# MRCS-IOX32.net
KiCad netlist of a schematic drawn in EAGLE
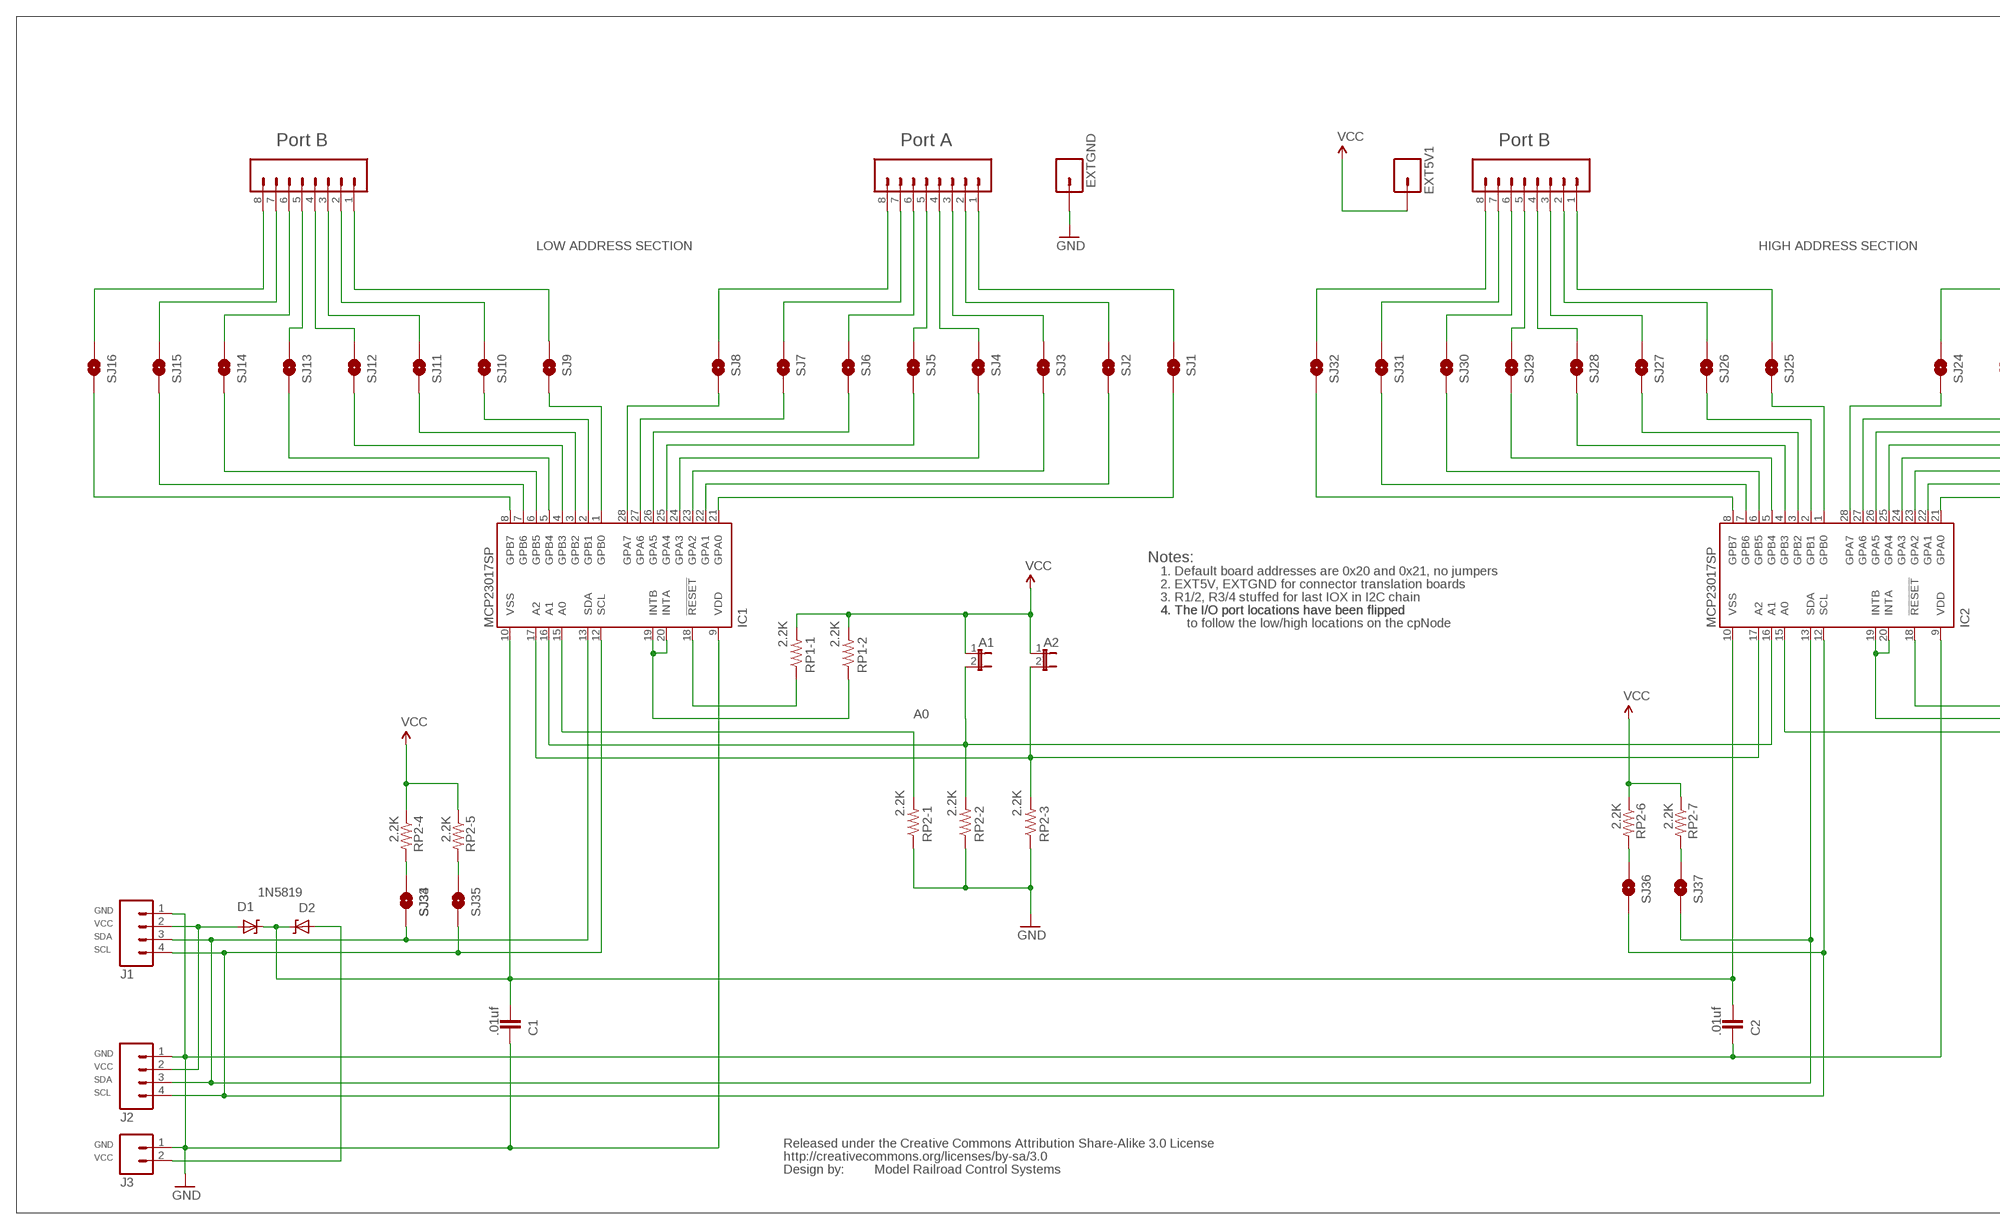
[diagram p0: schematic, sheet 1, part 1 of 2]
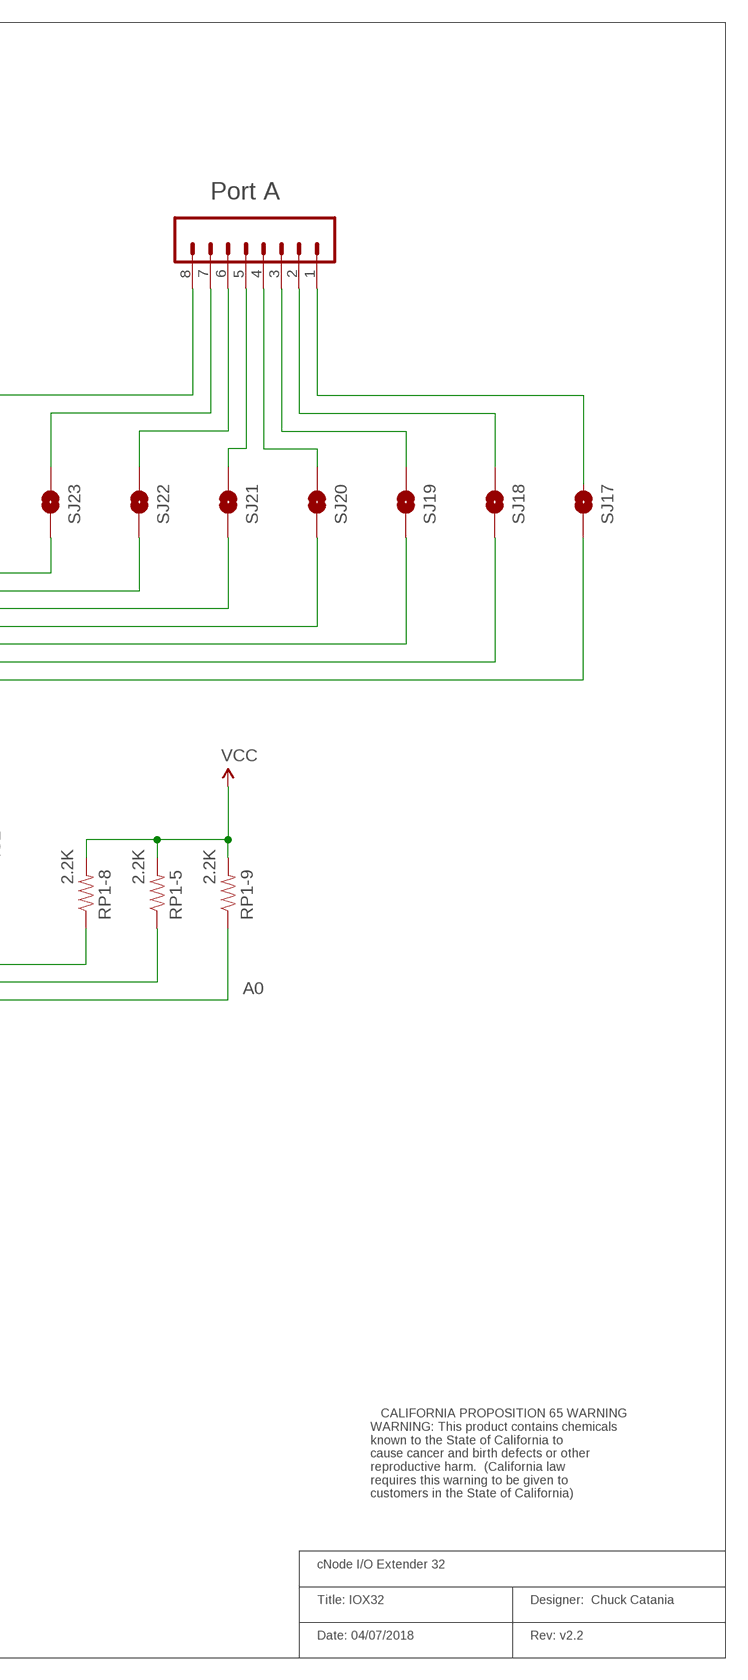
[diagram p1: schematic, sheet 1, part 2 of 2]

(export (version "E")
  (design (tool "Eeschema 10.0.6"))
  (components
    (comp (ref "A1")
      (value "JUMPER-2PTH")
      (footprint "eagle-import:1X02")
      (libsource (lib "eagle-import") (part "JUMPER-2PTH"))
    )
    (comp (ref "A2")
      (value "JUMPER-2PTH")
      (footprint "eagle-import:1X02")
      (libsource (lib "eagle-import") (part "JUMPER-2PTH"))
    )
    (comp (ref "C1")
      (value ".01uf")
      (footprint "eagle-import:AXIAL-5MM")
      (libsource (lib "eagle-import") (part "CAP_"))
    )
    (comp (ref "C2")
      (value ".01uf")
      (footprint "eagle-import:AXIAL-5MM")
      (libsource (lib "eagle-import") (part "CAP_"))
    )
    (comp (ref "D1")
      (value "DIODE-ZENERPTH")
      (footprint "eagle-import:DIODE-ZENER")
      (libsource (lib "eagle-import") (part "DIODE-ZENERPTH"))
    )
    (comp (ref "D2")
      (value "DIODE-ZENERPTH")
      (footprint "eagle-import:DIODE-ZENER")
      (libsource (lib "eagle-import") (part "DIODE-ZENERPTH"))
    )
    (comp (ref "EXT5V1")
      (value "M01PTH_LONGPAD")
      (footprint "eagle-import:1X01_LONGPAD")
      (libsource (lib "eagle-import") (part "M01PTH_LONGPAD"))
    )
    (comp (ref "EXTGND")
      (value "M01PTH_LONGPAD")
      (footprint "eagle-import:1X01_LONGPAD")
      (libsource (lib "eagle-import") (part "M01PTH_LONGPAD"))
    )
    (comp (ref "IC1")
      (value "MCP23017SP")
      (footprint "eagle-import:DIL28-3")
      (fields (field (name "MF") "MICROCHIP") (field (name "MPN") "MCP23017-E/SP"))
      (libsource (lib "eagle-import") (part "MCP23017SP"))
    )
    (comp (ref "IC2")
      (value "MCP23017SP")
      (footprint "eagle-import:DIL28-3")
      (fields (field (name "MF") "MICROCHIP") (field (name "MPN") "MCP23017-E/SP"))
      (libsource (lib "eagle-import") (part "MCP23017SP"))
    )
    (comp (ref "J1")
      (value "M04PTH")
      (footprint "eagle-import:1X04")
      (libsource (lib "eagle-import") (part "M04PTH"))
    )
    (comp (ref "J2")
      (value "M04PTH")
      (footprint "eagle-import:1X04")
      (libsource (lib "eagle-import") (part "M04PTH"))
    )
    (comp (ref "J3")
      (value "M021X02_NO_SILK")
      (footprint "eagle-import:1X02_NO_SILK")
      (libsource (lib "eagle-import") (part "M021X02_NO_SILK"))
    )
    (comp (ref "PORTA")
      (value "M081X08")
      (footprint "eagle-import:1X08")
      (libsource (lib "eagle-import") (part "M081X08"))
    )
    (comp (ref "PORTA1")
      (value "M081X08")
      (footprint "eagle-import:1X08")
      (libsource (lib "eagle-import") (part "M081X08"))
    )
    (comp (ref "PORTB")
      (value "M081X08")
      (footprint "eagle-import:1X08")
      (libsource (lib "eagle-import") (part "M081X08"))
    )
    (comp (ref "PORTB1")
      (value "M081X08")
      (footprint "eagle-import:1X08")
      (libsource (lib "eagle-import") (part "M081X08"))
    )
    (comp (ref "RP1-1")
      (value "2.2K")
      (footprint "eagle-import:AXIAL-0.4")
      (libsource (lib "eagle-import") (part "RESISTORPTH-1/4W"))
    )
    (comp (ref "RP1-2")
      (value "2.2K")
      (footprint "eagle-import:AXIAL-0.4")
      (libsource (lib "eagle-import") (part "RESISTORPTH-1/4W"))
    )
    (comp (ref "RP1-5")
      (value "2.2K")
      (footprint "eagle-import:AXIAL-0.4")
      (libsource (lib "eagle-import") (part "RESISTORPTH-1/4W"))
    )
    (comp (ref "RP1-8")
      (value "2.2K")
      (footprint "eagle-import:AXIAL-0.4")
      (libsource (lib "eagle-import") (part "RESISTORPTH-1/4W"))
    )
    (comp (ref "RP1-9")
      (value "2.2K")
      (footprint "eagle-import:AXIAL-0.4")
      (libsource (lib "eagle-import") (part "RESISTORPTH-1/4W"))
    )
    (comp (ref "RP2-1")
      (value "2.2K")
      (footprint "eagle-import:AXIAL-0.4")
      (libsource (lib "eagle-import") (part "RESISTORPTH-1/4W"))
    )
    (comp (ref "RP2-2")
      (value "2.2K")
      (footprint "eagle-import:AXIAL-0.4")
      (libsource (lib "eagle-import") (part "RESISTORPTH-1/4W"))
    )
    (comp (ref "RP2-3")
      (value "2.2K")
      (footprint "eagle-import:AXIAL-0.4")
      (libsource (lib "eagle-import") (part "RESISTORPTH-1/4W"))
    )
    (comp (ref "RP2-4")
      (value "2.2K")
      (footprint "eagle-import:AXIAL-0.4")
      (libsource (lib "eagle-import") (part "RESISTORPTH-1/4W"))
    )
    (comp (ref "RP2-5")
      (value "2.2K")
      (footprint "eagle-import:AXIAL-0.4")
      (libsource (lib "eagle-import") (part "RESISTORPTH-1/4W"))
    )
    (comp (ref "RP2-6")
      (value "2.2K")
      (footprint "eagle-import:AXIAL-0.4")
      (libsource (lib "eagle-import") (part "RESISTORPTH-1/4W"))
    )
    (comp (ref "RP2-7")
      (value "2.2K")
      (footprint "eagle-import:AXIAL-0.4")
      (libsource (lib "eagle-import") (part "RESISTORPTH-1/4W"))
    )
    (comp (ref "SJ1")
      (value "PAD-SOLDERJUMPERNC")
      (footprint "eagle-import:2P-SMD-2X3.3")
      (libsource (lib "eagle-import") (part "PAD-SOLDERJUMPERNC"))
    )
    (comp (ref "SJ2")
      (value "PAD-SOLDERJUMPERNC")
      (footprint "eagle-import:2P-SMD-2X3.3")
      (libsource (lib "eagle-import") (part "PAD-SOLDERJUMPERNC"))
    )
    (comp (ref "SJ3")
      (value "PAD-SOLDERJUMPERNC")
      (footprint "eagle-import:2P-SMD-2X3.3")
      (libsource (lib "eagle-import") (part "PAD-SOLDERJUMPERNC"))
    )
    (comp (ref "SJ4")
      (value "PAD-SOLDERJUMPERNC")
      (footprint "eagle-import:2P-SMD-2X3.3")
      (libsource (lib "eagle-import") (part "PAD-SOLDERJUMPERNC"))
    )
    (comp (ref "SJ5")
      (value "PAD-SOLDERJUMPERNC")
      (footprint "eagle-import:2P-SMD-2X3.3")
      (libsource (lib "eagle-import") (part "PAD-SOLDERJUMPERNC"))
    )
    (comp (ref "SJ6")
      (value "PAD-SOLDERJUMPERNC")
      (footprint "eagle-import:2P-SMD-2X3.3")
      (libsource (lib "eagle-import") (part "PAD-SOLDERJUMPERNC"))
    )
    (comp (ref "SJ7")
      (value "PAD-SOLDERJUMPERNC")
      (footprint "eagle-import:2P-SMD-2X3.3")
      (libsource (lib "eagle-import") (part "PAD-SOLDERJUMPERNC"))
    )
    (comp (ref "SJ8")
      (value "PAD-SOLDERJUMPERNC")
      (footprint "eagle-import:2P-SMD-2X3.3")
      (libsource (lib "eagle-import") (part "PAD-SOLDERJUMPERNC"))
    )
    (comp (ref "SJ9")
      (value "PAD-SOLDERJUMPERNC")
      (footprint "eagle-import:2P-SMD-2X3.3")
      (libsource (lib "eagle-import") (part "PAD-SOLDERJUMPERNC"))
    )
    (comp (ref "SJ10")
      (value "PAD-SOLDERJUMPERNC")
      (footprint "eagle-import:2P-SMD-2X3.3")
      (libsource (lib "eagle-import") (part "PAD-SOLDERJUMPERNC"))
    )
    (comp (ref "SJ11")
      (value "PAD-SOLDERJUMPERNC")
      (footprint "eagle-import:2P-SMD-2X3.3")
      (libsource (lib "eagle-import") (part "PAD-SOLDERJUMPERNC"))
    )
    (comp (ref "SJ12")
      (value "PAD-SOLDERJUMPERNC")
      (footprint "eagle-import:2P-SMD-2X3.3")
      (libsource (lib "eagle-import") (part "PAD-SOLDERJUMPERNC"))
    )
    (comp (ref "SJ13")
      (value "PAD-SOLDERJUMPERNC")
      (footprint "eagle-import:2P-SMD-2X3.3")
      (libsource (lib "eagle-import") (part "PAD-SOLDERJUMPERNC"))
    )
    (comp (ref "SJ14")
      (value "PAD-SOLDERJUMPERNC")
      (footprint "eagle-import:2P-SMD-2X3.3")
      (libsource (lib "eagle-import") (part "PAD-SOLDERJUMPERNC"))
    )
    (comp (ref "SJ15")
      (value "PAD-SOLDERJUMPERNC")
      (footprint "eagle-import:2P-SMD-2X3.3")
      (libsource (lib "eagle-import") (part "PAD-SOLDERJUMPERNC"))
    )
    (comp (ref "SJ16")
      (value "PAD-SOLDERJUMPERNC")
      (footprint "eagle-import:2P-SMD-2X3.3")
      (libsource (lib "eagle-import") (part "PAD-SOLDERJUMPERNC"))
    )
    (comp (ref "SJ17")
      (value "PAD-SOLDERJUMPERNC")
      (footprint "eagle-import:2P-SMD-2X3.3")
      (libsource (lib "eagle-import") (part "PAD-SOLDERJUMPERNC"))
    )
    (comp (ref "SJ18")
      (value "PAD-SOLDERJUMPERNC")
      (footprint "eagle-import:2P-SMD-2X3.3")
      (libsource (lib "eagle-import") (part "PAD-SOLDERJUMPERNC"))
    )
    (comp (ref "SJ19")
      (value "PAD-SOLDERJUMPERNC")
      (footprint "eagle-import:2P-SMD-2X3.3")
      (libsource (lib "eagle-import") (part "PAD-SOLDERJUMPERNC"))
    )
    (comp (ref "SJ20")
      (value "PAD-SOLDERJUMPERNC")
      (footprint "eagle-import:2P-SMD-2X3.3")
      (libsource (lib "eagle-import") (part "PAD-SOLDERJUMPERNC"))
    )
    (comp (ref "SJ21")
      (value "PAD-SOLDERJUMPERNC")
      (footprint "eagle-import:2P-SMD-2X3.3")
      (libsource (lib "eagle-import") (part "PAD-SOLDERJUMPERNC"))
    )
    (comp (ref "SJ22")
      (value "PAD-SOLDERJUMPERNC")
      (footprint "eagle-import:2P-SMD-2X3.3")
      (libsource (lib "eagle-import") (part "PAD-SOLDERJUMPERNC"))
    )
    (comp (ref "SJ23")
      (value "PAD-SOLDERJUMPERNC")
      (footprint "eagle-import:2P-SMD-2X3.3")
      (libsource (lib "eagle-import") (part "PAD-SOLDERJUMPERNC"))
    )
    (comp (ref "SJ24")
      (value "PAD-SOLDERJUMPERNC")
      (footprint "eagle-import:2P-SMD-2X3.3")
      (libsource (lib "eagle-import") (part "PAD-SOLDERJUMPERNC"))
    )
    (comp (ref "SJ25")
      (value "PAD-SOLDERJUMPERNC")
      (footprint "eagle-import:2P-SMD-2X3.3")
      (libsource (lib "eagle-import") (part "PAD-SOLDERJUMPERNC"))
    )
    (comp (ref "SJ26")
      (value "PAD-SOLDERJUMPERNC")
      (footprint "eagle-import:2P-SMD-2X3.3")
      (libsource (lib "eagle-import") (part "PAD-SOLDERJUMPERNC"))
    )
    (comp (ref "SJ27")
      (value "PAD-SOLDERJUMPERNC")
      (footprint "eagle-import:2P-SMD-2X3.3")
      (libsource (lib "eagle-import") (part "PAD-SOLDERJUMPERNC"))
    )
    (comp (ref "SJ28")
      (value "PAD-SOLDERJUMPERNC")
      (footprint "eagle-import:2P-SMD-2X3.3")
      (libsource (lib "eagle-import") (part "PAD-SOLDERJUMPERNC"))
    )
    (comp (ref "SJ29")
      (value "PAD-SOLDERJUMPERNC")
      (footprint "eagle-import:2P-SMD-2X3.3")
      (libsource (lib "eagle-import") (part "PAD-SOLDERJUMPERNC"))
    )
    (comp (ref "SJ30")
      (value "PAD-SOLDERJUMPERNC")
      (footprint "eagle-import:2P-SMD-2X3.3")
      (libsource (lib "eagle-import") (part "PAD-SOLDERJUMPERNC"))
    )
    (comp (ref "SJ31")
      (value "PAD-SOLDERJUMPERNC")
      (footprint "eagle-import:2P-SMD-2X3.3")
      (libsource (lib "eagle-import") (part "PAD-SOLDERJUMPERNC"))
    )
    (comp (ref "SJ32")
      (value "PAD-SOLDERJUMPERNC")
      (footprint "eagle-import:2P-SMD-2X3.3")
      (libsource (lib "eagle-import") (part "PAD-SOLDERJUMPERNC"))
    )
    (comp (ref "SJ33")
      (value "PAD-SOLDERJUMPERNC")
      (footprint "eagle-import:2P-SMD-2X3.3")
      (libsource (lib "eagle-import") (part "PAD-SOLDERJUMPERNC"))
    )
    (comp (ref "SJ34")
      (value "PAD-SOLDERJUMPERNC")
      (footprint "eagle-import:2P-SMD-2X3.3")
      (libsource (lib "eagle-import") (part "PAD-SOLDERJUMPERNC"))
    )
    (comp (ref "SJ35")
      (value "PAD-SOLDERJUMPERNC")
      (footprint "eagle-import:2P-SMD-2X3.3")
      (libsource (lib "eagle-import") (part "PAD-SOLDERJUMPERNC"))
    )
    (comp (ref "SJ36")
      (value "PAD-SOLDERJUMPERNC")
      (footprint "eagle-import:2P-SMD-2X3.3")
      (libsource (lib "eagle-import") (part "PAD-SOLDERJUMPERNC"))
    )
    (comp (ref "SJ37")
      (value "PAD-SOLDERJUMPERNC")
      (footprint "eagle-import:2P-SMD-2X3.3")
      (libsource (lib "eagle-import") (part "PAD-SOLDERJUMPERNC"))
    )
    (comp (ref "U$1")
      (value "CREATIVE_COMMONS")
      (footprint "eagle-import:CREATIVE_COMMONS")
      (libsource (lib "eagle-import") (part "CREATIVE_COMMONS"))
    )
    (comp (ref "U$2")
      (value "CA-PROP65WARNING")
      (footprint "eagle-import:CA-PROP65WARNING")
      (libsource (lib "eagle-import") (part "CA-PROP65WARNING"))
    )
  )
  (nets
    (net (code "1") (name "GND") (class "Default")
      (node (ref "C1") (pin "P$1") (pinfunction "1_P$1") (pintype "passive"))
      (node (ref "C2") (pin "P$1") (pinfunction "1_P$1") (pintype "passive"))
      (node (ref "EXTGND") (pin "1") (pinfunction "1_1") (pintype "passive"))
      (node (ref "IC1") (pin "9") (pinfunction "VDD_9") (pintype "power_in"))
      (node (ref "IC2") (pin "9") (pinfunction "VDD_9") (pintype "power_in"))
      (node (ref "J1") (pin "1") (pinfunction "1_1") (pintype "passive"))
      (node (ref "J2") (pin "1") (pinfunction "1_1") (pintype "passive"))
      (node (ref "J3") (pin "1") (pinfunction "1_1") (pintype "passive"))
      (node (ref "RP2-1") (pin "P$1") (pinfunction "1_P$1") (pintype "passive"))
      (node (ref "RP2-2") (pin "P$1") (pinfunction "1_P$1") (pintype "passive"))
      (node (ref "RP2-3") (pin "P$1") (pinfunction "1_P$1") (pintype "passive"))
    )
    (net (code "2") (name "Net-(C1-2)") (class "Default")
      (node (ref "C1") (pin "P$2") (pinfunction "2_P$2") (pintype "passive"))
      (node (ref "C2") (pin "P$2") (pinfunction "2_P$2") (pintype "passive"))
      (node (ref "D1") (pin "P$1") (pinfunction "C_P$1") (pintype "passive"))
      (node (ref "D2") (pin "P$1") (pinfunction "C_P$1") (pintype "passive"))
      (node (ref "IC1") (pin "10") (pinfunction "VSS_10") (pintype "power_in"))
      (node (ref "IC2") (pin "10") (pinfunction "VSS_10") (pintype "power_in"))
    )
    (net (code "3") (name "Net-(D1-A)") (class "Default")
      (node (ref "D1") (pin "P$2") (pinfunction "A_P$2") (pintype "passive"))
      (node (ref "J1") (pin "2") (pinfunction "2_2") (pintype "passive"))
      (node (ref "J2") (pin "2") (pinfunction "2_2") (pintype "passive"))
    )
    (net (code "4") (name "Net-(D2-A)") (class "Default")
      (node (ref "D2") (pin "P$2") (pinfunction "A_P$2") (pintype "passive"))
      (node (ref "J3") (pin "2") (pinfunction "2_2") (pintype "passive"))
    )
    (net (code "5") (name "Net-(IC1-A0)") (class "Default")
      (node (ref "IC1") (pin "15") (pinfunction "A0_15") (pintype "input"))
      (node (ref "RP2-1") (pin "P$2") (pinfunction "2_P$2") (pintype "passive"))
    )
    (net (code "6") (name "Net-(IC1-A1)") (class "Default")
      (node (ref "A1") (pin "2") (pinfunction "2_2") (pintype "passive"))
      (node (ref "IC1") (pin "16") (pinfunction "A1_16") (pintype "input"))
      (node (ref "IC2") (pin "16") (pinfunction "A1_16") (pintype "input"))
      (node (ref "RP2-2") (pin "P$2") (pinfunction "2_P$2") (pintype "passive"))
    )
    (net (code "7") (name "Net-(IC1-A2)") (class "Default")
      (node (ref "A2") (pin "2") (pinfunction "2_2") (pintype "passive"))
      (node (ref "IC1") (pin "17") (pinfunction "A2_17") (pintype "input"))
      (node (ref "IC2") (pin "17") (pinfunction "A2_17") (pintype "input"))
      (node (ref "RP2-3") (pin "P$2") (pinfunction "2_P$2") (pintype "passive"))
    )
    (net (code "8") (name "Net-(IC1-GPA0)") (class "Default")
      (node (ref "IC1") (pin "21") (pinfunction "GPA0_21") (pintype "bidirectional"))
      (node (ref "SJ1") (pin "2") (pinfunction "2_2") (pintype "passive"))
    )
    (net (code "9") (name "Net-(IC1-GPA1)") (class "Default")
      (node (ref "IC1") (pin "22") (pinfunction "GPA1_22") (pintype "bidirectional"))
      (node (ref "SJ2") (pin "2") (pinfunction "2_2") (pintype "passive"))
    )
    (net (code "10") (name "Net-(IC1-GPA2)") (class "Default")
      (node (ref "IC1") (pin "23") (pinfunction "GPA2_23") (pintype "bidirectional"))
      (node (ref "SJ3") (pin "2") (pinfunction "2_2") (pintype "passive"))
    )
    (net (code "11") (name "Net-(IC1-GPA3)") (class "Default")
      (node (ref "IC1") (pin "24") (pinfunction "GPA3_24") (pintype "bidirectional"))
      (node (ref "SJ4") (pin "2") (pinfunction "2_2") (pintype "passive"))
    )
    (net (code "12") (name "Net-(IC1-GPA4)") (class "Default")
      (node (ref "IC1") (pin "25") (pinfunction "GPA4_25") (pintype "bidirectional"))
      (node (ref "SJ5") (pin "2") (pinfunction "2_2") (pintype "passive"))
    )
    (net (code "13") (name "Net-(IC1-GPA5)") (class "Default")
      (node (ref "IC1") (pin "26") (pinfunction "GPA5_26") (pintype "bidirectional"))
      (node (ref "SJ6") (pin "2") (pinfunction "2_2") (pintype "passive"))
    )
    (net (code "14") (name "Net-(IC1-GPA6)") (class "Default")
      (node (ref "IC1") (pin "27") (pinfunction "GPA6_27") (pintype "bidirectional"))
      (node (ref "SJ7") (pin "2") (pinfunction "2_2") (pintype "passive"))
    )
    (net (code "15") (name "Net-(IC1-GPA7)") (class "Default")
      (node (ref "IC1") (pin "28") (pinfunction "GPA7_28") (pintype "bidirectional"))
      (node (ref "SJ8") (pin "2") (pinfunction "2_2") (pintype "passive"))
    )
    (net (code "16") (name "Net-(IC1-GPB0)") (class "Default")
      (node (ref "IC1") (pin "1") (pinfunction "GPB0_1") (pintype "bidirectional"))
      (node (ref "SJ9") (pin "2") (pinfunction "2_2") (pintype "passive"))
    )
    (net (code "17") (name "Net-(IC1-GPB1)") (class "Default")
      (node (ref "IC1") (pin "2") (pinfunction "GPB1_2") (pintype "bidirectional"))
      (node (ref "SJ10") (pin "2") (pinfunction "2_2") (pintype "passive"))
    )
    (net (code "18") (name "Net-(IC1-GPB2)") (class "Default")
      (node (ref "IC1") (pin "3") (pinfunction "GPB2_3") (pintype "bidirectional"))
      (node (ref "SJ11") (pin "2") (pinfunction "2_2") (pintype "passive"))
    )
    (net (code "19") (name "Net-(IC1-GPB3)") (class "Default")
      (node (ref "IC1") (pin "4") (pinfunction "GPB3_4") (pintype "bidirectional"))
      (node (ref "SJ12") (pin "2") (pinfunction "2_2") (pintype "passive"))
    )
    (net (code "20") (name "Net-(IC1-GPB4)") (class "Default")
      (node (ref "IC1") (pin "5") (pinfunction "GPB4_5") (pintype "bidirectional"))
      (node (ref "SJ13") (pin "2") (pinfunction "2_2") (pintype "passive"))
    )
    (net (code "21") (name "Net-(IC1-GPB5)") (class "Default")
      (node (ref "IC1") (pin "6") (pinfunction "GPB5_6") (pintype "bidirectional"))
      (node (ref "SJ14") (pin "2") (pinfunction "2_2") (pintype "passive"))
    )
    (net (code "22") (name "Net-(IC1-GPB6)") (class "Default")
      (node (ref "IC1") (pin "7") (pinfunction "GPB6_7") (pintype "bidirectional"))
      (node (ref "SJ15") (pin "2") (pinfunction "2_2") (pintype "passive"))
    )
    (net (code "23") (name "Net-(IC1-GPB7)") (class "Default")
      (node (ref "IC1") (pin "8") (pinfunction "GPB7_8") (pintype "bidirectional"))
      (node (ref "SJ16") (pin "2") (pinfunction "2_2") (pintype "passive"))
    )
    (net (code "24") (name "Net-(IC1-INTA)") (class "Default")
      (node (ref "IC1") (pin "19") (pinfunction "INTB_19") (pintype "output"))
      (node (ref "IC1") (pin "20") (pinfunction "INTA_20") (pintype "output"))
      (node (ref "RP1-2") (pin "P$1") (pinfunction "1_P$1") (pintype "passive"))
    )
    (net (code "25") (name "Net-(IC1-SCL)") (class "Default")
      (node (ref "IC1") (pin "12") (pinfunction "SCL_12") (pintype "input"))
      (node (ref "IC2") (pin "12") (pinfunction "SCL_12") (pintype "input"))
      (node (ref "J1") (pin "4") (pinfunction "4_4") (pintype "passive"))
      (node (ref "J2") (pin "4") (pinfunction "4_4") (pintype "passive"))
      (node (ref "SJ35") (pin "2") (pinfunction "2_2") (pintype "passive"))
      (node (ref "SJ36") (pin "2") (pinfunction "2_2") (pintype "passive"))
    )
    (net (code "26") (name "Net-(IC1-SDA)") (class "Default")
      (node (ref "IC1") (pin "13") (pinfunction "SDA_13") (pintype "bidirectional"))
      (node (ref "IC2") (pin "13") (pinfunction "SDA_13") (pintype "bidirectional"))
      (node (ref "J1") (pin "3") (pinfunction "3_3") (pintype "passive"))
      (node (ref "J2") (pin "3") (pinfunction "3_3") (pintype "passive"))
      (node (ref "SJ33") (pin "2") (pinfunction "2_2") (pintype "passive"))
      (node (ref "SJ34") (pin "2") (pinfunction "2_2") (pintype "passive"))
      (node (ref "SJ37") (pin "2") (pinfunction "2_2") (pintype "passive"))
    )
    (net (code "27") (name "Net-(IC1-~{RESET})") (class "Default")
      (node (ref "IC1") (pin "18") (pinfunction "~{RESET}_18") (pintype "input"))
      (node (ref "RP1-1") (pin "P$1") (pinfunction "1_P$1") (pintype "passive"))
    )
    (net (code "28") (name "Net-(IC2-A0)") (class "Default")
      (node (ref "IC2") (pin "15") (pinfunction "A0_15") (pintype "input"))
      (node (ref "RP1-9") (pin "P$1") (pinfunction "1_P$1") (pintype "passive"))
    )
    (net (code "29") (name "Net-(IC2-GPA0)") (class "Default")
      (node (ref "IC2") (pin "21") (pinfunction "GPA0_21") (pintype "bidirectional"))
      (node (ref "SJ17") (pin "2") (pinfunction "2_2") (pintype "passive"))
    )
    (net (code "30") (name "Net-(IC2-GPA1)") (class "Default")
      (node (ref "IC2") (pin "22") (pinfunction "GPA1_22") (pintype "bidirectional"))
      (node (ref "SJ18") (pin "2") (pinfunction "2_2") (pintype "passive"))
    )
    (net (code "31") (name "Net-(IC2-GPA2)") (class "Default")
      (node (ref "IC2") (pin "23") (pinfunction "GPA2_23") (pintype "bidirectional"))
      (node (ref "SJ19") (pin "2") (pinfunction "2_2") (pintype "passive"))
    )
    (net (code "32") (name "Net-(IC2-GPA3)") (class "Default")
      (node (ref "IC2") (pin "24") (pinfunction "GPA3_24") (pintype "bidirectional"))
      (node (ref "SJ20") (pin "2") (pinfunction "2_2") (pintype "passive"))
    )
    (net (code "33") (name "Net-(IC2-GPA4)") (class "Default")
      (node (ref "IC2") (pin "25") (pinfunction "GPA4_25") (pintype "bidirectional"))
      (node (ref "SJ21") (pin "2") (pinfunction "2_2") (pintype "passive"))
    )
    (net (code "34") (name "Net-(IC2-GPA5)") (class "Default")
      (node (ref "IC2") (pin "26") (pinfunction "GPA5_26") (pintype "bidirectional"))
      (node (ref "SJ22") (pin "2") (pinfunction "2_2") (pintype "passive"))
    )
    (net (code "35") (name "Net-(IC2-GPA6)") (class "Default")
      (node (ref "IC2") (pin "27") (pinfunction "GPA6_27") (pintype "bidirectional"))
      (node (ref "SJ23") (pin "2") (pinfunction "2_2") (pintype "passive"))
    )
    (net (code "36") (name "Net-(IC2-GPA7)") (class "Default")
      (node (ref "IC2") (pin "28") (pinfunction "GPA7_28") (pintype "bidirectional"))
      (node (ref "SJ24") (pin "2") (pinfunction "2_2") (pintype "passive"))
    )
    (net (code "37") (name "Net-(IC2-GPB0)") (class "Default")
      (node (ref "IC2") (pin "1") (pinfunction "GPB0_1") (pintype "bidirectional"))
      (node (ref "SJ25") (pin "2") (pinfunction "2_2") (pintype "passive"))
    )
    (net (code "38") (name "Net-(IC2-GPB1)") (class "Default")
      (node (ref "IC2") (pin "2") (pinfunction "GPB1_2") (pintype "bidirectional"))
      (node (ref "SJ26") (pin "2") (pinfunction "2_2") (pintype "passive"))
    )
    (net (code "39") (name "Net-(IC2-GPB2)") (class "Default")
      (node (ref "IC2") (pin "3") (pinfunction "GPB2_3") (pintype "bidirectional"))
      (node (ref "SJ27") (pin "2") (pinfunction "2_2") (pintype "passive"))
    )
    (net (code "40") (name "Net-(IC2-GPB3)") (class "Default")
      (node (ref "IC2") (pin "4") (pinfunction "GPB3_4") (pintype "bidirectional"))
      (node (ref "SJ28") (pin "2") (pinfunction "2_2") (pintype "passive"))
    )
    (net (code "41") (name "Net-(IC2-GPB4)") (class "Default")
      (node (ref "IC2") (pin "5") (pinfunction "GPB4_5") (pintype "bidirectional"))
      (node (ref "SJ29") (pin "2") (pinfunction "2_2") (pintype "passive"))
    )
    (net (code "42") (name "Net-(IC2-GPB5)") (class "Default")
      (node (ref "IC2") (pin "6") (pinfunction "GPB5_6") (pintype "bidirectional"))
      (node (ref "SJ30") (pin "2") (pinfunction "2_2") (pintype "passive"))
    )
    (net (code "43") (name "Net-(IC2-GPB6)") (class "Default")
      (node (ref "IC2") (pin "7") (pinfunction "GPB6_7") (pintype "bidirectional"))
      (node (ref "SJ31") (pin "2") (pinfunction "2_2") (pintype "passive"))
    )
    (net (code "44") (name "Net-(IC2-GPB7)") (class "Default")
      (node (ref "IC2") (pin "8") (pinfunction "GPB7_8") (pintype "bidirectional"))
      (node (ref "SJ32") (pin "2") (pinfunction "2_2") (pintype "passive"))
    )
    (net (code "45") (name "Net-(IC2-INTA)") (class "Default")
      (node (ref "IC2") (pin "19") (pinfunction "INTB_19") (pintype "output"))
      (node (ref "IC2") (pin "20") (pinfunction "INTA_20") (pintype "output"))
      (node (ref "RP1-5") (pin "P$1") (pinfunction "1_P$1") (pintype "passive"))
    )
    (net (code "46") (name "Net-(IC2-~{RESET})") (class "Default")
      (node (ref "IC2") (pin "18") (pinfunction "~{RESET}_18") (pintype "input"))
      (node (ref "RP1-8") (pin "P$1") (pinfunction "1_P$1") (pintype "passive"))
    )
    (net (code "47") (name "Net-(PORTA-Pad1)") (class "Default")
      (node (ref "PORTA") (pin "1") (pinfunction "1_1") (pintype "passive"))
      (node (ref "SJ1") (pin "1") (pinfunction "1_1") (pintype "passive"))
    )
    (net (code "48") (name "Net-(PORTA-Pad2)") (class "Default")
      (node (ref "PORTA") (pin "2") (pinfunction "2_2") (pintype "passive"))
      (node (ref "SJ2") (pin "1") (pinfunction "1_1") (pintype "passive"))
    )
    (net (code "49") (name "Net-(PORTA-Pad3)") (class "Default")
      (node (ref "PORTA") (pin "3") (pinfunction "3_3") (pintype "passive"))
      (node (ref "SJ3") (pin "1") (pinfunction "1_1") (pintype "passive"))
    )
    (net (code "50") (name "Net-(PORTA-Pad4)") (class "Default")
      (node (ref "PORTA") (pin "4") (pinfunction "4_4") (pintype "passive"))
      (node (ref "SJ4") (pin "1") (pinfunction "1_1") (pintype "passive"))
    )
    (net (code "51") (name "Net-(PORTA-Pad5)") (class "Default")
      (node (ref "PORTA") (pin "5") (pinfunction "5_5") (pintype "passive"))
      (node (ref "SJ5") (pin "1") (pinfunction "1_1") (pintype "passive"))
    )
    (net (code "52") (name "Net-(PORTA-Pad6)") (class "Default")
      (node (ref "PORTA") (pin "6") (pinfunction "6_6") (pintype "passive"))
      (node (ref "SJ6") (pin "1") (pinfunction "1_1") (pintype "passive"))
    )
    (net (code "53") (name "Net-(PORTA-Pad7)") (class "Default")
      (node (ref "PORTA") (pin "7") (pinfunction "7_7") (pintype "passive"))
      (node (ref "SJ7") (pin "1") (pinfunction "1_1") (pintype "passive"))
    )
    (net (code "54") (name "Net-(PORTA-Pad8)") (class "Default")
      (node (ref "PORTA") (pin "8") (pinfunction "8_8") (pintype "passive"))
      (node (ref "SJ8") (pin "1") (pinfunction "1_1") (pintype "passive"))
    )
    (net (code "55") (name "Net-(PORTA1-Pad1)") (class "Default")
      (node (ref "PORTA1") (pin "1") (pinfunction "1_1") (pintype "passive"))
      (node (ref "SJ17") (pin "1") (pinfunction "1_1") (pintype "passive"))
    )
    (net (code "56") (name "Net-(PORTA1-Pad2)") (class "Default")
      (node (ref "PORTA1") (pin "2") (pinfunction "2_2") (pintype "passive"))
      (node (ref "SJ18") (pin "1") (pinfunction "1_1") (pintype "passive"))
    )
    (net (code "57") (name "Net-(PORTA1-Pad3)") (class "Default")
      (node (ref "PORTA1") (pin "3") (pinfunction "3_3") (pintype "passive"))
      (node (ref "SJ19") (pin "1") (pinfunction "1_1") (pintype "passive"))
    )
    (net (code "58") (name "Net-(PORTA1-Pad4)") (class "Default")
      (node (ref "PORTA1") (pin "4") (pinfunction "4_4") (pintype "passive"))
      (node (ref "SJ20") (pin "1") (pinfunction "1_1") (pintype "passive"))
    )
    (net (code "59") (name "Net-(PORTA1-Pad5)") (class "Default")
      (node (ref "PORTA1") (pin "5") (pinfunction "5_5") (pintype "passive"))
      (node (ref "SJ21") (pin "1") (pinfunction "1_1") (pintype "passive"))
    )
    (net (code "60") (name "Net-(PORTA1-Pad6)") (class "Default")
      (node (ref "PORTA1") (pin "6") (pinfunction "6_6") (pintype "passive"))
      (node (ref "SJ22") (pin "1") (pinfunction "1_1") (pintype "passive"))
    )
    (net (code "61") (name "Net-(PORTA1-Pad7)") (class "Default")
      (node (ref "PORTA1") (pin "7") (pinfunction "7_7") (pintype "passive"))
      (node (ref "SJ23") (pin "1") (pinfunction "1_1") (pintype "passive"))
    )
    (net (code "62") (name "Net-(PORTA1-Pad8)") (class "Default")
      (node (ref "PORTA1") (pin "8") (pinfunction "8_8") (pintype "passive"))
      (node (ref "SJ24") (pin "1") (pinfunction "1_1") (pintype "passive"))
    )
    (net (code "63") (name "Net-(PORTB-Pad1)") (class "Default")
      (node (ref "PORTB") (pin "1") (pinfunction "1_1") (pintype "passive"))
      (node (ref "SJ9") (pin "1") (pinfunction "1_1") (pintype "passive"))
    )
    (net (code "64") (name "Net-(PORTB-Pad2)") (class "Default")
      (node (ref "PORTB") (pin "2") (pinfunction "2_2") (pintype "passive"))
      (node (ref "SJ10") (pin "1") (pinfunction "1_1") (pintype "passive"))
    )
    (net (code "65") (name "Net-(PORTB-Pad3)") (class "Default")
      (node (ref "PORTB") (pin "3") (pinfunction "3_3") (pintype "passive"))
      (node (ref "SJ11") (pin "1") (pinfunction "1_1") (pintype "passive"))
    )
    (net (code "66") (name "Net-(PORTB-Pad4)") (class "Default")
      (node (ref "PORTB") (pin "4") (pinfunction "4_4") (pintype "passive"))
      (node (ref "SJ12") (pin "1") (pinfunction "1_1") (pintype "passive"))
    )
    (net (code "67") (name "Net-(PORTB-Pad5)") (class "Default")
      (node (ref "PORTB") (pin "5") (pinfunction "5_5") (pintype "passive"))
      (node (ref "SJ13") (pin "1") (pinfunction "1_1") (pintype "passive"))
    )
    (net (code "68") (name "Net-(PORTB-Pad6)") (class "Default")
      (node (ref "PORTB") (pin "6") (pinfunction "6_6") (pintype "passive"))
      (node (ref "SJ14") (pin "1") (pinfunction "1_1") (pintype "passive"))
    )
    (net (code "69") (name "Net-(PORTB-Pad7)") (class "Default")
      (node (ref "PORTB") (pin "7") (pinfunction "7_7") (pintype "passive"))
      (node (ref "SJ15") (pin "1") (pinfunction "1_1") (pintype "passive"))
    )
    (net (code "70") (name "Net-(PORTB-Pad8)") (class "Default")
      (node (ref "PORTB") (pin "8") (pinfunction "8_8") (pintype "passive"))
      (node (ref "SJ16") (pin "1") (pinfunction "1_1") (pintype "passive"))
    )
    (net (code "71") (name "Net-(PORTB1-Pad1)") (class "Default")
      (node (ref "PORTB1") (pin "1") (pinfunction "1_1") (pintype "passive"))
      (node (ref "SJ25") (pin "1") (pinfunction "1_1") (pintype "passive"))
    )
    (net (code "72") (name "Net-(PORTB1-Pad2)") (class "Default")
      (node (ref "PORTB1") (pin "2") (pinfunction "2_2") (pintype "passive"))
      (node (ref "SJ26") (pin "1") (pinfunction "1_1") (pintype "passive"))
    )
    (net (code "73") (name "Net-(PORTB1-Pad3)") (class "Default")
      (node (ref "PORTB1") (pin "3") (pinfunction "3_3") (pintype "passive"))
      (node (ref "SJ27") (pin "1") (pinfunction "1_1") (pintype "passive"))
    )
    (net (code "74") (name "Net-(PORTB1-Pad4)") (class "Default")
      (node (ref "PORTB1") (pin "4") (pinfunction "4_4") (pintype "passive"))
      (node (ref "SJ28") (pin "1") (pinfunction "1_1") (pintype "passive"))
    )
    (net (code "75") (name "Net-(PORTB1-Pad5)") (class "Default")
      (node (ref "PORTB1") (pin "5") (pinfunction "5_5") (pintype "passive"))
      (node (ref "SJ29") (pin "1") (pinfunction "1_1") (pintype "passive"))
    )
    (net (code "76") (name "Net-(PORTB1-Pad6)") (class "Default")
      (node (ref "PORTB1") (pin "6") (pinfunction "6_6") (pintype "passive"))
      (node (ref "SJ30") (pin "1") (pinfunction "1_1") (pintype "passive"))
    )
    (net (code "77") (name "Net-(PORTB1-Pad7)") (class "Default")
      (node (ref "PORTB1") (pin "7") (pinfunction "7_7") (pintype "passive"))
      (node (ref "SJ31") (pin "1") (pinfunction "1_1") (pintype "passive"))
    )
    (net (code "78") (name "Net-(PORTB1-Pad8)") (class "Default")
      (node (ref "PORTB1") (pin "8") (pinfunction "8_8") (pintype "passive"))
      (node (ref "SJ32") (pin "1") (pinfunction "1_1") (pintype "passive"))
    )
    (net (code "79") (name "Net-(RP2-4-2)") (class "Default")
      (node (ref "RP2-4") (pin "P$2") (pinfunction "2_P$2") (pintype "passive"))
      (node (ref "SJ33") (pin "1") (pinfunction "1_1") (pintype "passive"))
      (node (ref "SJ34") (pin "1") (pinfunction "1_1") (pintype "passive"))
    )
    (net (code "80") (name "Net-(RP2-5-2)") (class "Default")
      (node (ref "RP2-5") (pin "P$2") (pinfunction "2_P$2") (pintype "passive"))
      (node (ref "SJ35") (pin "1") (pinfunction "1_1") (pintype "passive"))
    )
    (net (code "81") (name "Net-(RP2-6-2)") (class "Default")
      (node (ref "RP2-6") (pin "P$2") (pinfunction "2_P$2") (pintype "passive"))
      (node (ref "SJ36") (pin "1") (pinfunction "1_1") (pintype "passive"))
    )
    (net (code "82") (name "Net-(RP2-7-2)") (class "Default")
      (node (ref "RP2-7") (pin "P$2") (pinfunction "2_P$2") (pintype "passive"))
      (node (ref "SJ37") (pin "1") (pinfunction "1_1") (pintype "passive"))
    )
    (net (code "83") (name "VCC") (class "Default")
      (node (ref "A1") (pin "1") (pinfunction "1_1") (pintype "passive"))
      (node (ref "A2") (pin "1") (pinfunction "1_1") (pintype "passive"))
      (node (ref "EXT5V1") (pin "1") (pinfunction "1_1") (pintype "passive"))
      (node (ref "RP1-1") (pin "P$2") (pinfunction "2_P$2") (pintype "passive"))
      (node (ref "RP1-2") (pin "P$2") (pinfunction "2_P$2") (pintype "passive"))
      (node (ref "RP1-5") (pin "P$2") (pinfunction "2_P$2") (pintype "passive"))
      (node (ref "RP1-8") (pin "P$2") (pinfunction "2_P$2") (pintype "passive"))
      (node (ref "RP1-9") (pin "P$2") (pinfunction "2_P$2") (pintype "passive"))
      (node (ref "RP2-4") (pin "P$1") (pinfunction "1_P$1") (pintype "passive"))
      (node (ref "RP2-5") (pin "P$1") (pinfunction "1_P$1") (pintype "passive"))
      (node (ref "RP2-6") (pin "P$1") (pinfunction "1_P$1") (pintype "passive"))
      (node (ref "RP2-7") (pin "P$1") (pinfunction "1_P$1") (pintype "passive"))
    )
  )
)
